# irma_nano.net
KiCad netlist of a schematic drawn in EAGLE
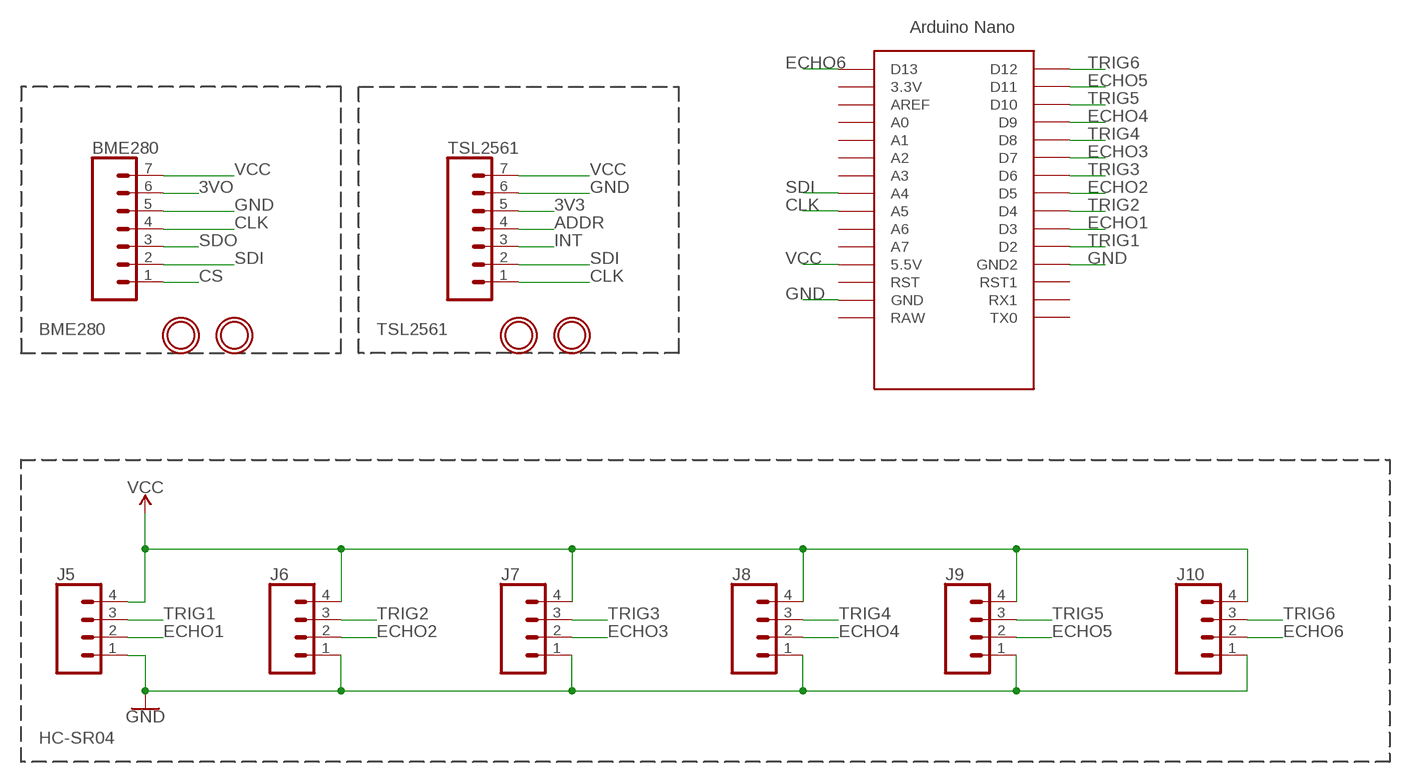
[diagram p0: schematic, sheet 1]

(export (version "E")
  (design (tool "Eeschema 10.0.6"))
  (components
    (comp (ref "BME280")
      (value "CONN_07")
      (footprint "eagle-import:1X07")
      (libsource (lib "eagle-import") (part "CONN_07"))
    )
    (comp (ref "J5")
      (value "CONN_04")
      (footprint "eagle-import:1X04")
      (libsource (lib "eagle-import") (part "CONN_04"))
    )
    (comp (ref "J6")
      (value "CONN_04")
      (footprint "eagle-import:1X04")
      (libsource (lib "eagle-import") (part "CONN_04"))
    )
    (comp (ref "J7")
      (value "CONN_04")
      (footprint "eagle-import:1X04")
      (libsource (lib "eagle-import") (part "CONN_04"))
    )
    (comp (ref "J8")
      (value "CONN_04")
      (footprint "eagle-import:1X04")
      (libsource (lib "eagle-import") (part "CONN_04"))
    )
    (comp (ref "J9")
      (value "CONN_04")
      (footprint "eagle-import:1X04")
      (libsource (lib "eagle-import") (part "CONN_04"))
    )
    (comp (ref "J10")
      (value "CONN_04")
      (footprint "eagle-import:1X04")
      (libsource (lib "eagle-import") (part "CONN_04"))
    )
    (comp (ref "TSL2561")
      (value "CONN_07")
      (footprint "eagle-import:1X07")
      (libsource (lib "eagle-import") (part "CONN_07"))
    )
    (comp (ref "U$1")
      (value "MOUNTINGHOLE2.0")
      (footprint "eagle-import:MOUNTINGHOLE_2.0_PLATED")
      (libsource (lib "eagle-import") (part "MOUNTINGHOLE2.0"))
    )
    (comp (ref "U$2")
      (value "MOUNTINGHOLE2.0")
      (footprint "eagle-import:MOUNTINGHOLE_2.0_PLATED")
      (libsource (lib "eagle-import") (part "MOUNTINGHOLE2.0"))
    )
    (comp (ref "U$3")
      (value "MOUNTINGHOLE2.5")
      (footprint "eagle-import:MOUNTINGHOLE_2.5_PLATED")
      (libsource (lib "eagle-import") (part "MOUNTINGHOLE2.5"))
    )
    (comp (ref "U$4")
      (value "MOUNTINGHOLE2.5")
      (footprint "eagle-import:MOUNTINGHOLE_2.5_PLATED")
      (libsource (lib "eagle-import") (part "MOUNTINGHOLE2.5"))
    )
    (comp (ref "U$5")
      (value "NANO")
      (footprint "eagle-import:NANO")
      (libsource (lib "eagle-import") (part "NANO"))
    )
  )
  (nets
    (net (code "1") (name "/3V3") (class "Default")
      (node (ref "TSL2561") (pin "5") (pinfunction "5_5") (pintype "passive"))
    )
    (net (code "2") (name "/3VO") (class "Default")
      (node (ref "BME280") (pin "6") (pinfunction "6_6") (pintype "passive"))
    )
    (net (code "3") (name "/ADDR") (class "Default")
      (node (ref "TSL2561") (pin "4") (pinfunction "4_4") (pintype "passive"))
    )
    (net (code "4") (name "/CLK") (class "Default")
      (node (ref "BME280") (pin "4") (pinfunction "4_4") (pintype "passive"))
      (node (ref "TSL2561") (pin "1") (pinfunction "1_1") (pintype "passive"))
      (node (ref "U$5") (pin "A5") (pinfunction "A5_A5") (pintype "bidirectional"))
    )
    (net (code "5") (name "/CS") (class "Default")
      (node (ref "BME280") (pin "1") (pinfunction "1_1") (pintype "passive"))
    )
    (net (code "6") (name "/ECHO1") (class "Default")
      (node (ref "J5") (pin "2") (pinfunction "2_2") (pintype "passive"))
      (node (ref "U$5") (pin "D3") (pinfunction "D3_D3") (pintype "bidirectional"))
    )
    (net (code "7") (name "/ECHO2") (class "Default")
      (node (ref "J6") (pin "2") (pinfunction "2_2") (pintype "passive"))
      (node (ref "U$5") (pin "D5") (pinfunction "D5_D5") (pintype "bidirectional"))
    )
    (net (code "8") (name "/ECHO3") (class "Default")
      (node (ref "J7") (pin "2") (pinfunction "2_2") (pintype "passive"))
      (node (ref "U$5") (pin "D7") (pinfunction "D7_D7") (pintype "bidirectional"))
    )
    (net (code "9") (name "/ECHO4") (class "Default")
      (node (ref "J8") (pin "2") (pinfunction "2_2") (pintype "passive"))
      (node (ref "U$5") (pin "D9") (pinfunction "D9_D9") (pintype "bidirectional"))
    )
    (net (code "10") (name "/ECHO5") (class "Default")
      (node (ref "J9") (pin "2") (pinfunction "2_2") (pintype "passive"))
      (node (ref "U$5") (pin "D11") (pinfunction "D11_D11") (pintype "bidirectional"))
    )
    (net (code "11") (name "/ECHO6") (class "Default")
      (node (ref "J10") (pin "2") (pinfunction "2_2") (pintype "passive"))
      (node (ref "U$5") (pin "D13") (pinfunction "D13_D13") (pintype "bidirectional"))
    )
    (net (code "12") (name "/INT") (class "Default")
      (node (ref "TSL2561") (pin "3") (pinfunction "3_3") (pintype "passive"))
    )
    (net (code "13") (name "/SDI") (class "Default")
      (node (ref "BME280") (pin "2") (pinfunction "2_2") (pintype "passive"))
      (node (ref "TSL2561") (pin "2") (pinfunction "2_2") (pintype "passive"))
      (node (ref "U$5") (pin "A4") (pinfunction "A4_A4") (pintype "bidirectional"))
    )
    (net (code "14") (name "/SDO") (class "Default")
      (node (ref "BME280") (pin "3") (pinfunction "3_3") (pintype "passive"))
    )
    (net (code "15") (name "/TRIG1") (class "Default")
      (node (ref "J5") (pin "3") (pinfunction "3_3") (pintype "passive"))
      (node (ref "U$5") (pin "D2") (pinfunction "D2_D2") (pintype "bidirectional"))
    )
    (net (code "16") (name "/TRIG2") (class "Default")
      (node (ref "J6") (pin "3") (pinfunction "3_3") (pintype "passive"))
      (node (ref "U$5") (pin "D4") (pinfunction "D4_D4") (pintype "bidirectional"))
    )
    (net (code "17") (name "/TRIG3") (class "Default")
      (node (ref "J7") (pin "3") (pinfunction "3_3") (pintype "passive"))
      (node (ref "U$5") (pin "D6") (pinfunction "D6_D6") (pintype "bidirectional"))
    )
    (net (code "18") (name "/TRIG4") (class "Default")
      (node (ref "J8") (pin "3") (pinfunction "3_3") (pintype "passive"))
      (node (ref "U$5") (pin "D8") (pinfunction "D8_D8") (pintype "bidirectional"))
    )
    (net (code "19") (name "/TRIG5") (class "Default")
      (node (ref "J9") (pin "3") (pinfunction "3_3") (pintype "passive"))
      (node (ref "U$5") (pin "D10") (pinfunction "D10_D10") (pintype "bidirectional"))
    )
    (net (code "20") (name "/TRIG6") (class "Default")
      (node (ref "J10") (pin "3") (pinfunction "3_3") (pintype "passive"))
      (node (ref "U$5") (pin "D12") (pinfunction "D12_D12") (pintype "bidirectional"))
    )
    (net (code "21") (name "GND") (class "Default")
      (node (ref "BME280") (pin "5") (pinfunction "5_5") (pintype "passive"))
      (node (ref "J10") (pin "1") (pinfunction "1_1") (pintype "passive"))
      (node (ref "J5") (pin "1") (pinfunction "1_1") (pintype "passive"))
      (node (ref "J6") (pin "1") (pinfunction "1_1") (pintype "passive"))
      (node (ref "J7") (pin "1") (pinfunction "1_1") (pintype "passive"))
      (node (ref "J8") (pin "1") (pinfunction "1_1") (pintype "passive"))
      (node (ref "J9") (pin "1") (pinfunction "1_1") (pintype "passive"))
      (node (ref "TSL2561") (pin "6") (pinfunction "6_6") (pintype "passive"))
      (node (ref "U$5") (pin "GND") (pinfunction "GND_GND") (pintype "bidirectional"))
      (node (ref "U$5") (pin "GND1") (pinfunction "GND2_GND1") (pintype "bidirectional"))
    )
    (net (code "22") (name "VCC") (class "Default")
      (node (ref "BME280") (pin "7") (pinfunction "7_7") (pintype "passive"))
      (node (ref "J10") (pin "4") (pinfunction "4_4") (pintype "passive"))
      (node (ref "J5") (pin "4") (pinfunction "4_4") (pintype "passive"))
      (node (ref "J6") (pin "4") (pinfunction "4_4") (pintype "passive"))
      (node (ref "J7") (pin "4") (pinfunction "4_4") (pintype "passive"))
      (node (ref "J8") (pin "4") (pinfunction "4_4") (pintype "passive"))
      (node (ref "J9") (pin "4") (pinfunction "4_4") (pintype "passive"))
      (node (ref "TSL2561") (pin "7") (pinfunction "7_7") (pintype "passive"))
      (node (ref "U$5") (pin "5V") (pinfunction "5.5V_5V") (pintype "bidirectional"))
    )
    (net (code "23") (name "unconnected-(U$5-Pad3.3V)") (class "Default")
      (node (ref "U$5") (pin "3.3V") (pinfunction "3.3V_3.3V") (pintype "bidirectional"))
    )
    (net (code "24") (name "unconnected-(U$5-PadA0)") (class "Default")
      (node (ref "U$5") (pin "A0") (pinfunction "A0_A0") (pintype "bidirectional"))
    )
    (net (code "25") (name "unconnected-(U$5-PadA1)") (class "Default")
      (node (ref "U$5") (pin "A1") (pinfunction "A1_A1") (pintype "bidirectional"))
    )
    (net (code "26") (name "unconnected-(U$5-PadA2)") (class "Default")
      (node (ref "U$5") (pin "A2") (pinfunction "A2_A2") (pintype "bidirectional"))
    )
    (net (code "27") (name "unconnected-(U$5-PadA3)") (class "Default")
      (node (ref "U$5") (pin "A3") (pinfunction "A3_A3") (pintype "bidirectional"))
    )
    (net (code "28") (name "unconnected-(U$5-PadA6)") (class "Default")
      (node (ref "U$5") (pin "A6") (pinfunction "A6_A6") (pintype "bidirectional"))
    )
    (net (code "29") (name "unconnected-(U$5-PadA7)") (class "Default")
      (node (ref "U$5") (pin "A7") (pinfunction "A7_A7") (pintype "bidirectional"))
    )
    (net (code "30") (name "unconnected-(U$5-PadAREF)") (class "Default")
      (node (ref "U$5") (pin "AREF") (pinfunction "AREF_AREF") (pintype "bidirectional"))
    )
    (net (code "31") (name "unconnected-(U$5-PadICSP1)") (class "Default")
      (node (ref "U$5") (pin "ICSP1") (pinfunction "ICSP1_ICSP1") (pintype "bidirectional"))
    )
    (net (code "32") (name "unconnected-(U$5-PadICSP2)") (class "Default")
      (node (ref "U$5") (pin "ICSP2") (pinfunction "ICSP2_ICSP2") (pintype "bidirectional"))
    )
    (net (code "33") (name "unconnected-(U$5-PadICSP3)") (class "Default")
      (node (ref "U$5") (pin "ICSP3") (pinfunction "ICSP3_ICSP3") (pintype "bidirectional"))
    )
    (net (code "34") (name "unconnected-(U$5-PadICSP4)") (class "Default")
      (node (ref "U$5") (pin "ICSP4") (pinfunction "ICSP4_ICSP4") (pintype "bidirectional"))
    )
    (net (code "35") (name "unconnected-(U$5-PadICSP5)") (class "Default")
      (node (ref "U$5") (pin "ICSP5") (pinfunction "ICSP5_ICSP5") (pintype "bidirectional"))
    )
    (net (code "36") (name "unconnected-(U$5-PadICSP6)") (class "Default")
      (node (ref "U$5") (pin "ICSP6") (pinfunction "ICSP6_ICSP6") (pintype "bidirectional"))
    )
    (net (code "37") (name "unconnected-(U$5-PadRAW)") (class "Default")
      (node (ref "U$5") (pin "RAW") (pinfunction "RAW_RAW") (pintype "bidirectional"))
    )
    (net (code "38") (name "unconnected-(U$5-PadRST)") (class "Default")
      (node (ref "U$5") (pin "RST") (pinfunction "RST_RST") (pintype "bidirectional"))
    )
    (net (code "39") (name "unconnected-(U$5-PadRST1)") (class "Default")
      (node (ref "U$5") (pin "RST1") (pinfunction "RST1_RST1") (pintype "bidirectional"))
    )
    (net (code "40") (name "unconnected-(U$5-PadRX1)") (class "Default")
      (node (ref "U$5") (pin "RX1") (pinfunction "RX1_RX1") (pintype "bidirectional"))
    )
    (net (code "41") (name "unconnected-(U$5-PadTX0)") (class "Default")
      (node (ref "U$5") (pin "TX0") (pinfunction "TX0_TX0") (pintype "bidirectional"))
    )
  )
)
